# hv_in3.net
KiCad netlist of a schematic drawn in EAGLE
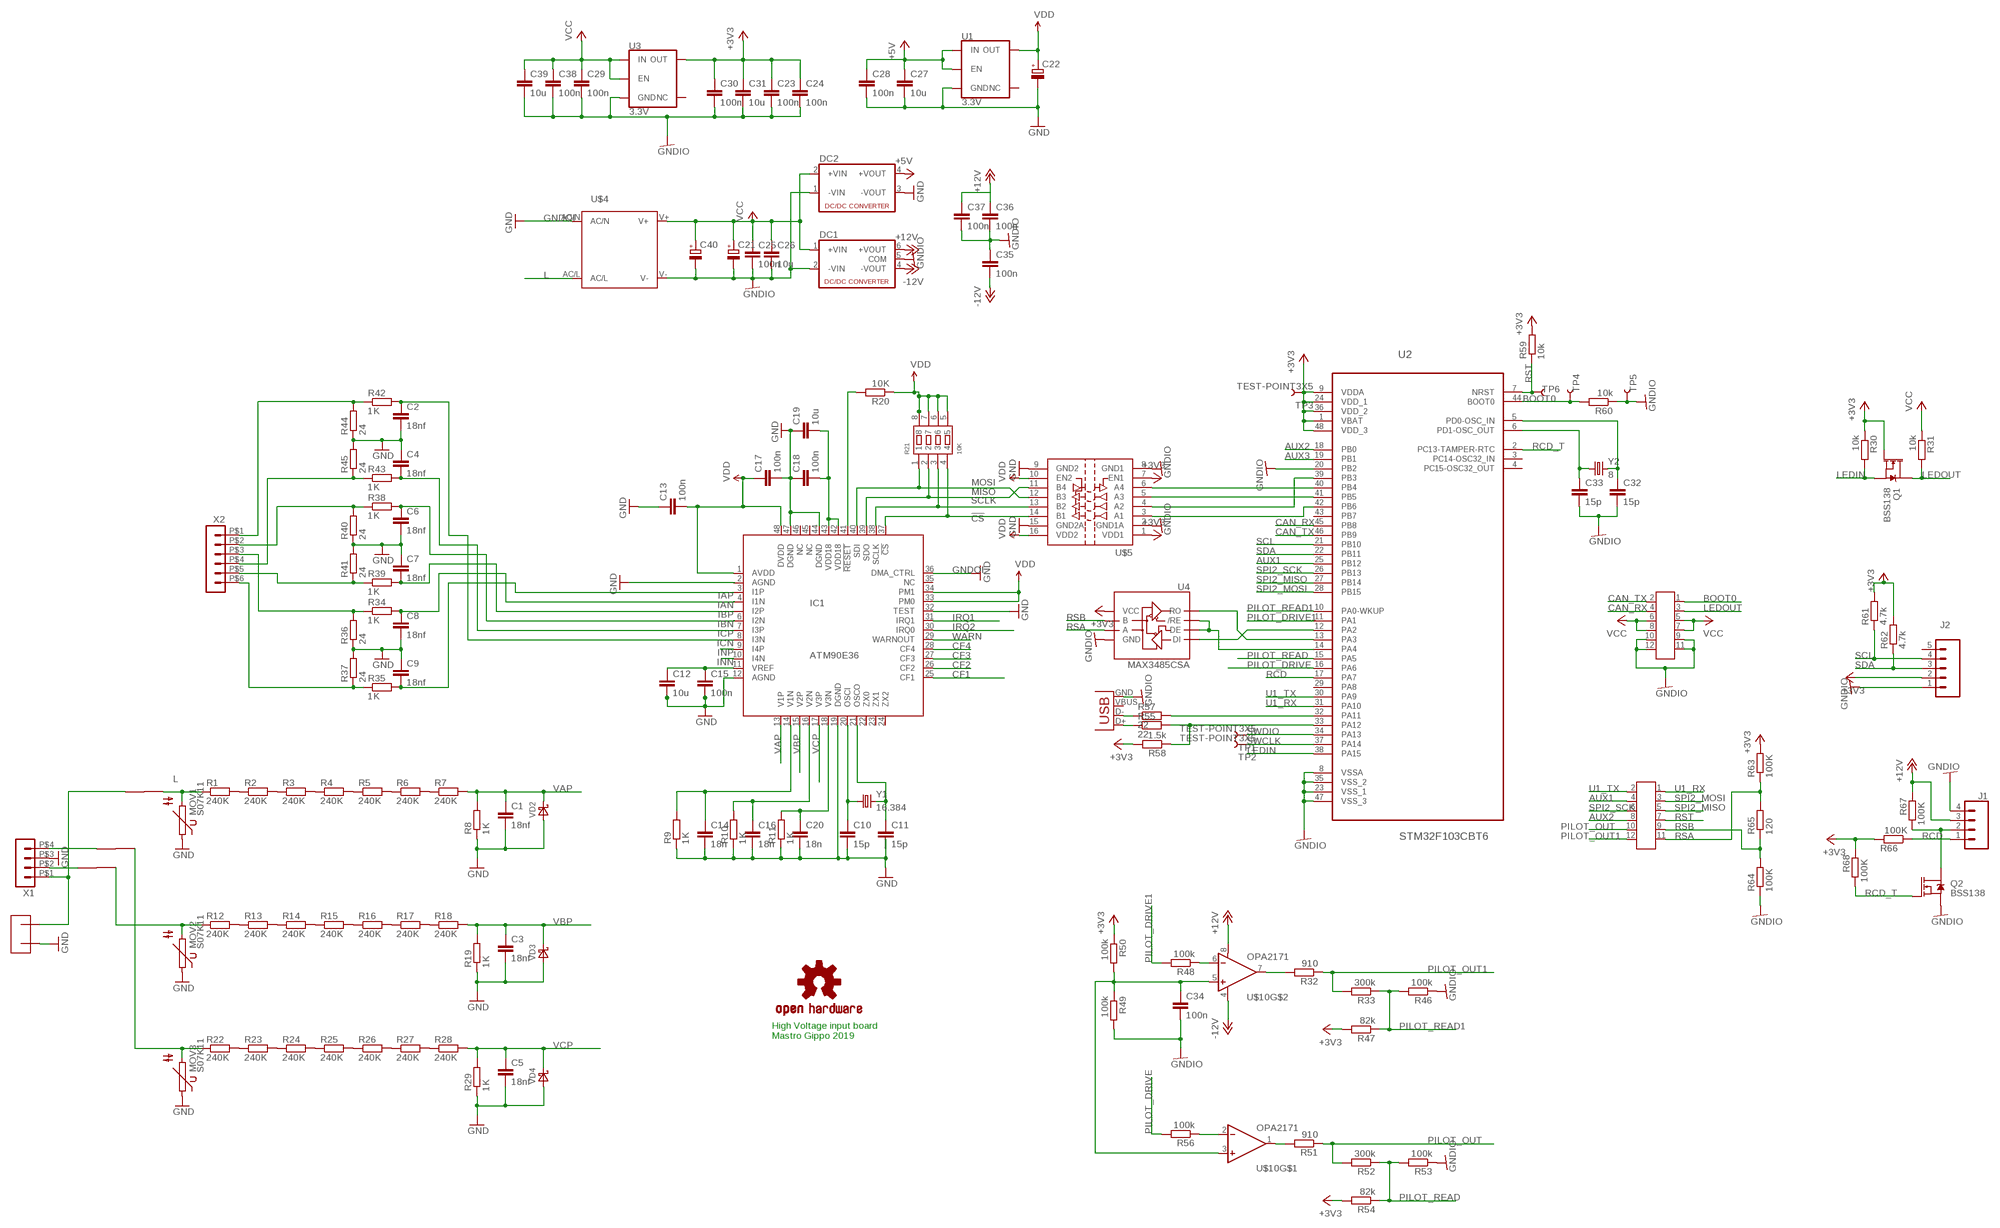
[diagram p0: schematic, sheet 1]

(export (version "E")
  (design (tool "Eeschema 10.0.6"))
  (components
    (comp (ref "C1")
      (value "18nf")
      (footprint "eagle-import:C0805K")
      (libsource (lib "eagle-import") (part "C-EUC0805K"))
    )
    (comp (ref "C2")
      (value "18nf")
      (footprint "eagle-import:C0805K")
      (libsource (lib "eagle-import") (part "C-EUC0805K"))
    )
    (comp (ref "C3")
      (value "18nf")
      (footprint "eagle-import:C0805K")
      (libsource (lib "eagle-import") (part "C-EUC0805K"))
    )
    (comp (ref "C4")
      (value "18nf")
      (footprint "eagle-import:C0805K")
      (libsource (lib "eagle-import") (part "C-EUC0805K"))
    )
    (comp (ref "C5")
      (value "18nf")
      (footprint "eagle-import:C0805K")
      (libsource (lib "eagle-import") (part "C-EUC0805K"))
    )
    (comp (ref "C6")
      (value "18nf")
      (footprint "eagle-import:C0805K")
      (libsource (lib "eagle-import") (part "C-EUC0805K"))
    )
    (comp (ref "C7")
      (value "18nf")
      (footprint "eagle-import:C0805K")
      (libsource (lib "eagle-import") (part "C-EUC0805K"))
    )
    (comp (ref "C8")
      (value "18nf")
      (footprint "eagle-import:C0805K")
      (libsource (lib "eagle-import") (part "C-EUC0805K"))
    )
    (comp (ref "C9")
      (value "18nf")
      (footprint "eagle-import:C0805K")
      (libsource (lib "eagle-import") (part "C-EUC0805K"))
    )
    (comp (ref "C10")
      (value "15p")
      (footprint "eagle-import:C0805K")
      (libsource (lib "eagle-import") (part "C-EUC0805K"))
    )
    (comp (ref "C11")
      (value "15p")
      (footprint "eagle-import:C0805K")
      (libsource (lib "eagle-import") (part "C-EUC0805K"))
    )
    (comp (ref "C12")
      (value "10u")
      (footprint "eagle-import:C0805K")
      (libsource (lib "eagle-import") (part "C-EUC0805K"))
    )
    (comp (ref "C13")
      (value "100n")
      (footprint "eagle-import:C0805K")
      (libsource (lib "eagle-import") (part "C-EUC0805K"))
    )
    (comp (ref "C14")
      (value "18n")
      (footprint "eagle-import:C0805K")
      (libsource (lib "eagle-import") (part "C-EUC0805K"))
    )
    (comp (ref "C15")
      (value "100n")
      (footprint "eagle-import:C0805K")
      (libsource (lib "eagle-import") (part "C-EUC0805K"))
    )
    (comp (ref "C16")
      (value "18n")
      (footprint "eagle-import:C0805K")
      (libsource (lib "eagle-import") (part "C-EUC0805K"))
    )
    (comp (ref "C17")
      (value "100n")
      (footprint "eagle-import:C0805K")
      (libsource (lib "eagle-import") (part "C-EUC0805K"))
    )
    (comp (ref "C18")
      (value "100n")
      (footprint "eagle-import:C0805K")
      (libsource (lib "eagle-import") (part "C-EUC0805K"))
    )
    (comp (ref "C19")
      (value "10u")
      (footprint "eagle-import:C0805K")
      (libsource (lib "eagle-import") (part "C-EUC0805K"))
    )
    (comp (ref "C20")
      (value "18n")
      (footprint "eagle-import:C0805K")
      (libsource (lib "eagle-import") (part "C-EUC0805K"))
    )
    (comp (ref "C21")
      (value "CPOL-EU153CLV-0505")
      (footprint "eagle-import:153CLV-0505")
      (libsource (lib "eagle-import") (part "CPOL-EU153CLV-0505"))
    )
    (comp (ref "C22")
      (value "CPOL-EU153CLV-0505")
      (footprint "eagle-import:153CLV-0505")
      (libsource (lib "eagle-import") (part "CPOL-EU153CLV-0505"))
    )
    (comp (ref "C23")
      (value "100n")
      (footprint "eagle-import:C0805K")
      (libsource (lib "eagle-import") (part "C-EUC0805K"))
    )
    (comp (ref "C24")
      (value "100n")
      (footprint "eagle-import:C0805K")
      (libsource (lib "eagle-import") (part "C-EUC0805K"))
    )
    (comp (ref "C25")
      (value "100n")
      (footprint "eagle-import:C0805K")
      (libsource (lib "eagle-import") (part "C-EUC0805K"))
    )
    (comp (ref "C26")
      (value "10u")
      (footprint "eagle-import:C0805K")
      (libsource (lib "eagle-import") (part "C-EUC0805K"))
    )
    (comp (ref "C27")
      (value "10u")
      (footprint "eagle-import:C0805K")
      (libsource (lib "eagle-import") (part "C-EUC0805K"))
    )
    (comp (ref "C28")
      (value "100n")
      (footprint "eagle-import:C0805K")
      (libsource (lib "eagle-import") (part "C-EUC0805K"))
    )
    (comp (ref "C29")
      (value "100n")
      (footprint "eagle-import:C0805K")
      (libsource (lib "eagle-import") (part "C-EUC0805K"))
    )
    (comp (ref "C30")
      (value "100n")
      (footprint "eagle-import:C0805K")
      (libsource (lib "eagle-import") (part "C-EUC0805K"))
    )
    (comp (ref "C31")
      (value "10u")
      (footprint "eagle-import:C0805K")
      (libsource (lib "eagle-import") (part "C-EUC0805K"))
    )
    (comp (ref "C32")
      (value "15p")
      (footprint "eagle-import:C0805K")
      (libsource (lib "eagle-import") (part "C-EUC0805K"))
    )
    (comp (ref "C33")
      (value "15p")
      (footprint "eagle-import:C0805K")
      (libsource (lib "eagle-import") (part "C-EUC0805K"))
    )
    (comp (ref "C34")
      (value "100n")
      (footprint "eagle-import:C0805K")
      (libsource (lib "eagle-import") (part "C-EUC0805K"))
    )
    (comp (ref "C35")
      (value "100n")
      (footprint "eagle-import:C0805K")
      (libsource (lib "eagle-import") (part "C-EUC0805K"))
    )
    (comp (ref "C36")
      (value "100n")
      (footprint "eagle-import:C0805K")
      (libsource (lib "eagle-import") (part "C-EUC0805K"))
    )
    (comp (ref "C37")
      (value "100n")
      (footprint "eagle-import:C0805K")
      (libsource (lib "eagle-import") (part "C-EUC0805K"))
    )
    (comp (ref "C38")
      (value "100n")
      (footprint "eagle-import:C0805K")
      (libsource (lib "eagle-import") (part "C-EUC0805K"))
    )
    (comp (ref "C39")
      (value "10u")
      (footprint "eagle-import:C0805K")
      (libsource (lib "eagle-import") (part "C-EUC0805K"))
    )
    (comp (ref "C40")
      (value "CPOL-EUB/3528-21R")
      (footprint "eagle-import:B_3528-21R")
      (libsource (lib "eagle-import") (part "CPOL-EUB/3528-21R"))
    )
    (comp (ref "DC1")
      (value "NMA")
      (footprint "eagle-import:NMA")
      (fields (field (name "MF") "C & D TECHNOLOGIES, INC") (field (name "MPN") "NMA0515SC"))
      (libsource (lib "eagle-import") (part "NMA"))
    )
    (comp (ref "DC2")
      (value "NME")
      (footprint "eagle-import:NME")
      (fields (field (name "MF") "C & D TECHNOLOGIES, INC") (field (name "MPN") "NME1205D"))
      (libsource (lib "eagle-import") (part "NME"))
    )
    (comp (ref "IC1")
      (value "ATM90E36")
      (footprint "eagle-import:TQFP48")
      (libsource (lib "eagle-import") (part "ATM90E36"))
    )
    (comp (ref "J1")
      (value "CONN_04SMD2")
      (footprint "eagle-import:1X04_1MM_RA")
      (libsource (lib "eagle-import") (part "CONN_04SMD2"))
    )
    (comp (ref "J2")
      (value "CONN_05SMD2")
      (footprint "eagle-import:1X05_1MM_RA")
      (libsource (lib "eagle-import") (part "CONN_05SMD2"))
    )
    (comp (ref "MOV1")
      (value "S07K11")
      (footprint "eagle-import:S07K11")
      (libsource (lib "eagle-import") (part "S07K11"))
    )
    (comp (ref "MOV2")
      (value "S07K11")
      (footprint "eagle-import:S07K11")
      (libsource (lib "eagle-import") (part "S07K11"))
    )
    (comp (ref "MOV3")
      (value "S07K11")
      (footprint "eagle-import:S07K11")
      (libsource (lib "eagle-import") (part "S07K11"))
    )
    (comp (ref "Q1")
      (value "BSS138")
      (footprint "eagle-import:SOT23-3")
      (libsource (lib "eagle-import") (part "MOSFET-NCH-BSS138"))
    )
    (comp (ref "Q2")
      (value "BSS138")
      (footprint "eagle-import:SOT23-3")
      (libsource (lib "eagle-import") (part "MOSFET-NCH-BSS138"))
    )
    (comp (ref "R1")
      (value "240K")
      (footprint "eagle-import:R0805")
      (libsource (lib "eagle-import") (part "R_EU"))
    )
    (comp (ref "R2")
      (value "240K")
      (footprint "eagle-import:R0805")
      (libsource (lib "eagle-import") (part "R_EU"))
    )
    (comp (ref "R3")
      (value "240K")
      (footprint "eagle-import:R0805")
      (libsource (lib "eagle-import") (part "R_EU"))
    )
    (comp (ref "R4")
      (value "240K")
      (footprint "eagle-import:R0805")
      (libsource (lib "eagle-import") (part "R_EU"))
    )
    (comp (ref "R5")
      (value "240K")
      (footprint "eagle-import:R0805")
      (libsource (lib "eagle-import") (part "R_EU"))
    )
    (comp (ref "R6")
      (value "240K")
      (footprint "eagle-import:R0805")
      (libsource (lib "eagle-import") (part "R_EU"))
    )
    (comp (ref "R7")
      (value "240K")
      (footprint "eagle-import:R0805")
      (libsource (lib "eagle-import") (part "R_EU"))
    )
    (comp (ref "R8")
      (value "1K")
      (footprint "eagle-import:R0805")
      (libsource (lib "eagle-import") (part "R_EU"))
    )
    (comp (ref "R9")
      (value "1K")
      (footprint "eagle-import:R0805")
      (libsource (lib "eagle-import") (part "R_EU"))
    )
    (comp (ref "R10")
      (value "1K")
      (footprint "eagle-import:R0805")
      (libsource (lib "eagle-import") (part "R_EU"))
    )
    (comp (ref "R11")
      (value "1K")
      (footprint "eagle-import:R0805")
      (libsource (lib "eagle-import") (part "R_EU"))
    )
    (comp (ref "R12")
      (value "240K")
      (footprint "eagle-import:R0805")
      (libsource (lib "eagle-import") (part "R_EU"))
    )
    (comp (ref "R13")
      (value "240K")
      (footprint "eagle-import:R0805")
      (libsource (lib "eagle-import") (part "R_EU"))
    )
    (comp (ref "R14")
      (value "240K")
      (footprint "eagle-import:R0805")
      (libsource (lib "eagle-import") (part "R_EU"))
    )
    (comp (ref "R15")
      (value "240K")
      (footprint "eagle-import:R0805")
      (libsource (lib "eagle-import") (part "R_EU"))
    )
    (comp (ref "R16")
      (value "240K")
      (footprint "eagle-import:R0805")
      (libsource (lib "eagle-import") (part "R_EU"))
    )
    (comp (ref "R17")
      (value "240K")
      (footprint "eagle-import:R0805")
      (libsource (lib "eagle-import") (part "R_EU"))
    )
    (comp (ref "R18")
      (value "240K")
      (footprint "eagle-import:R0805")
      (libsource (lib "eagle-import") (part "R_EU"))
    )
    (comp (ref "R19")
      (value "1K")
      (footprint "eagle-import:R0805")
      (libsource (lib "eagle-import") (part "R_EU"))
    )
    (comp (ref "R20")
      (value "10K")
      (footprint "eagle-import:R0805")
      (libsource (lib "eagle-import") (part "R_EU"))
    )
    (comp (ref "R21")
      (value "10K")
      (footprint "eagle-import:RA1206-8")
      (fields (field (name "MPN") "Chip-Array-Series-1%"))
      (libsource (lib "eagle-import") (part "SMD-RES-ARRAY-1K-4R(RA1206-8)"))
    )
    (comp (ref "R22")
      (value "240K")
      (footprint "eagle-import:R0805")
      (libsource (lib "eagle-import") (part "R_EU"))
    )
    (comp (ref "R23")
      (value "240K")
      (footprint "eagle-import:R0805")
      (libsource (lib "eagle-import") (part "R_EU"))
    )
    (comp (ref "R24")
      (value "240K")
      (footprint "eagle-import:R0805")
      (libsource (lib "eagle-import") (part "R_EU"))
    )
    (comp (ref "R25")
      (value "240K")
      (footprint "eagle-import:R0805")
      (libsource (lib "eagle-import") (part "R_EU"))
    )
    (comp (ref "R26")
      (value "240K")
      (footprint "eagle-import:R0805")
      (libsource (lib "eagle-import") (part "R_EU"))
    )
    (comp (ref "R27")
      (value "240K")
      (footprint "eagle-import:R0805")
      (libsource (lib "eagle-import") (part "R_EU"))
    )
    (comp (ref "R28")
      (value "240K")
      (footprint "eagle-import:R0805")
      (libsource (lib "eagle-import") (part "R_EU"))
    )
    (comp (ref "R29")
      (value "1K")
      (footprint "eagle-import:R0805")
      (libsource (lib "eagle-import") (part "R_EU"))
    )
    (comp (ref "R30")
      (value "10k")
      (footprint "eagle-import:R0805")
      (libsource (lib "eagle-import") (part "R-EU_R0805"))
    )
    (comp (ref "R31")
      (value "10k")
      (footprint "eagle-import:R0805")
      (libsource (lib "eagle-import") (part "R-EU_R0805"))
    )
    (comp (ref "R32")
      (value "910")
      (footprint "eagle-import:R1206")
      (libsource (lib "eagle-import") (part "R-EU_R1206"))
    )
    (comp (ref "R33")
      (value "300k")
      (footprint "eagle-import:R0805")
      (libsource (lib "eagle-import") (part "R-EU_R0805"))
    )
    (comp (ref "R34")
      (value "1K")
      (footprint "eagle-import:R0805")
      (libsource (lib "eagle-import") (part "R_EU"))
    )
    (comp (ref "R35")
      (value "1K")
      (footprint "eagle-import:R0805")
      (libsource (lib "eagle-import") (part "R_EU"))
    )
    (comp (ref "R36")
      (value "24")
      (footprint "eagle-import:R0805")
      (libsource (lib "eagle-import") (part "R_EU"))
    )
    (comp (ref "R37")
      (value "24")
      (footprint "eagle-import:R0805")
      (libsource (lib "eagle-import") (part "R_EU"))
    )
    (comp (ref "R38")
      (value "1K")
      (footprint "eagle-import:R0805")
      (libsource (lib "eagle-import") (part "R_EU"))
    )
    (comp (ref "R39")
      (value "1K")
      (footprint "eagle-import:R0805")
      (libsource (lib "eagle-import") (part "R_EU"))
    )
    (comp (ref "R40")
      (value "24")
      (footprint "eagle-import:R0805")
      (libsource (lib "eagle-import") (part "R_EU"))
    )
    (comp (ref "R41")
      (value "24")
      (footprint "eagle-import:R0805")
      (libsource (lib "eagle-import") (part "R_EU"))
    )
    (comp (ref "R42")
      (value "1K")
      (footprint "eagle-import:R0805")
      (libsource (lib "eagle-import") (part "R_EU"))
    )
    (comp (ref "R43")
      (value "1K")
      (footprint "eagle-import:R0805")
      (libsource (lib "eagle-import") (part "R_EU"))
    )
    (comp (ref "R44")
      (value "24")
      (footprint "eagle-import:R0805")
      (libsource (lib "eagle-import") (part "R_EU"))
    )
    (comp (ref "R45")
      (value "24")
      (footprint "eagle-import:R0805")
      (libsource (lib "eagle-import") (part "R_EU"))
    )
    (comp (ref "R46")
      (value "100k")
      (footprint "eagle-import:R0805")
      (libsource (lib "eagle-import") (part "R-EU_R0805"))
    )
    (comp (ref "R47")
      (value "82k")
      (footprint "eagle-import:R0805")
      (libsource (lib "eagle-import") (part "R-EU_R0805"))
    )
    (comp (ref "R48")
      (value "100k")
      (footprint "eagle-import:R0805")
      (libsource (lib "eagle-import") (part "R-EU_R0805"))
    )
    (comp (ref "R49")
      (value "100k")
      (footprint "eagle-import:R0805")
      (libsource (lib "eagle-import") (part "R-EU_R0805"))
    )
    (comp (ref "R50")
      (value "100k")
      (footprint "eagle-import:R0805")
      (libsource (lib "eagle-import") (part "R-EU_R0805"))
    )
    (comp (ref "R51")
      (value "910")
      (footprint "eagle-import:R1206")
      (libsource (lib "eagle-import") (part "R-EU_R1206"))
    )
    (comp (ref "R52")
      (value "300k")
      (footprint "eagle-import:R0805")
      (libsource (lib "eagle-import") (part "R-EU_R0805"))
    )
    (comp (ref "R53")
      (value "100k")
      (footprint "eagle-import:R0805")
      (libsource (lib "eagle-import") (part "R-EU_R0805"))
    )
    (comp (ref "R54")
      (value "82k")
      (footprint "eagle-import:R0805")
      (libsource (lib "eagle-import") (part "R-EU_R0805"))
    )
    (comp (ref "R55")
      (value "22")
      (footprint "eagle-import:R0805")
      (libsource (lib "eagle-import") (part "R-EU_R0805"))
    )
    (comp (ref "R56")
      (value "100k")
      (footprint "eagle-import:R0805")
      (libsource (lib "eagle-import") (part "R-EU_R0805"))
    )
    (comp (ref "R57")
      (value "22")
      (footprint "eagle-import:R0805")
      (libsource (lib "eagle-import") (part "R-EU_R0805"))
    )
    (comp (ref "R58")
      (value "1.5k")
      (footprint "eagle-import:R0805")
      (libsource (lib "eagle-import") (part "R-EU_R0805"))
    )
    (comp (ref "R59")
      (value "10k")
      (footprint "eagle-import:R0805")
      (libsource (lib "eagle-import") (part "R-EU_R0805"))
    )
    (comp (ref "R60")
      (value "10k")
      (footprint "eagle-import:R0805")
      (libsource (lib "eagle-import") (part "R-EU_R0805"))
    )
    (comp (ref "R61")
      (value "4.7k")
      (footprint "eagle-import:R0805")
      (libsource (lib "eagle-import") (part "R-EU_R0805"))
    )
    (comp (ref "R62")
      (value "4.7k")
      (footprint "eagle-import:R0805")
      (libsource (lib "eagle-import") (part "R-EU_R0805"))
    )
    (comp (ref "R63")
      (value "100K")
      (footprint "eagle-import:R0805")
      (libsource (lib "eagle-import") (part "R-EU_R0805"))
    )
    (comp (ref "R64")
      (value "100K")
      (footprint "eagle-import:R0805")
      (libsource (lib "eagle-import") (part "R-EU_R0805"))
    )
    (comp (ref "R65")
      (value "120")
      (footprint "eagle-import:R0805")
      (libsource (lib "eagle-import") (part "R-EU_R0805"))
    )
    (comp (ref "R66")
      (value "100K")
      (footprint "eagle-import:R0805")
      (libsource (lib "eagle-import") (part "R-EU_R0805"))
    )
    (comp (ref "R67")
      (value "100K")
      (footprint "eagle-import:R0805")
      (libsource (lib "eagle-import") (part "R-EU_R0805"))
    )
    (comp (ref "R68")
      (value "100K")
      (footprint "eagle-import:R0805")
      (libsource (lib "eagle-import") (part "R-EU_R0805"))
    )
    (comp (ref "TP1")
      (value "TEST-POINT3X5")
      (footprint "eagle-import:PAD.03X.05")
      (libsource (lib "eagle-import") (part "TEST-POINT3X5"))
    )
    (comp (ref "TP2")
      (value "TEST-POINT3X5")
      (footprint "eagle-import:PAD.03X.05")
      (libsource (lib "eagle-import") (part "TEST-POINT3X5"))
    )
    (comp (ref "TP3")
      (value "TEST-POINT3X5")
      (footprint "eagle-import:PAD.03X.05")
      (libsource (lib "eagle-import") (part "TEST-POINT3X5"))
    )
    (comp (ref "TP4")
      (value "TEST-POINT3X5")
      (footprint "eagle-import:PAD.03X.05")
      (libsource (lib "eagle-import") (part "TEST-POINT3X5"))
    )
    (comp (ref "TP5")
      (value "TEST-POINT3X5")
      (footprint "eagle-import:PAD.03X.05")
      (libsource (lib "eagle-import") (part "TEST-POINT3X5"))
    )
    (comp (ref "TP6")
      (value "TEST-POINT3X5")
      (footprint "eagle-import:PAD.03X.05")
      (libsource (lib "eagle-import") (part "TEST-POINT3X5"))
    )
    (comp (ref "U$1")
      (value "FUSE_2410")
      (footprint "eagle-import:2410_F")
      (libsource (lib "eagle-import") (part "FUSE_2410"))
    )
    (comp (ref "U$2")
      (value "FUSE_2410")
      (footprint "eagle-import:2410_F")
      (libsource (lib "eagle-import") (part "FUSE_2410"))
    )
    (comp (ref "U$3")
      (value "FUSE_2410")
      (footprint "eagle-import:2410_F")
      (libsource (lib "eagle-import") (part "FUSE_2410"))
    )
    (comp (ref "U$4")
      (value "IRM_15/20IRM_15/20")
      (footprint "eagle-import:IRM_15_20")
      (libsource (lib "eagle-import") (part "IRM_15/20IRM_15/20"))
    )
    (comp (ref "U$5")
      (value "SI8441IS1")
      (footprint "eagle-import:SO16")
      (libsource (lib "eagle-import") (part "SI8441IS1"))
    )
    (comp (ref "U$6")
      (value "ISOLATED_2P")
      (footprint "eagle-import:STRIP_NOMIDDLE")
      (libsource (lib "eagle-import") (part "ISOLATED_2P"))
    )
    (comp (ref "U$7")
      (value "CLP-106-02-F-D-P")
      (footprint "eagle-import:CLP-106-02-X-D")
      (libsource (lib "eagle-import") (part "CLP-106-02-F-D-P"))
    )
    (comp (ref "U$8")
      (value "CLP-106-02-F-D-P")
      (footprint "eagle-import:CLP-106-02-X-D")
      (libsource (lib "eagle-import") (part "CLP-106-02-F-D-P"))
    )
    (comp (ref "U$9")
      (value "OSHW-LOGOS")
      (footprint "eagle-import:OSHW-LOGO-S")
      (libsource (lib "eagle-import") (part "OSHW-LOGOS"))
    )
    (comp (ref "U$10")
      (value "OPA2171")
      (footprint "eagle-import:SO08")
      (libsource (lib "eagle-import") (part "OPA2171"))
    )
    (comp (ref "U1")
      (value "3.3V")
      (footprint "eagle-import:SOT23-5")
      (libsource (lib "eagle-import") (part "V_REG_AP2112K-3.3V"))
    )
    (comp (ref "U2")
      (value "STM32F103CBT6")
      (footprint "eagle-import:QFP50P900X900X160-48N")
      (libsource (lib "eagle-import") (part "STM32F103CBT6"))
    )
    (comp (ref "U3")
      (value "3.3V")
      (footprint "eagle-import:SOT23-5")
      (libsource (lib "eagle-import") (part "V_REG_AP2112K-3.3V"))
    )
    (comp (ref "U4")
      (value "MAX3485CSA")
      (footprint "eagle-import:SO08")
      (libsource (lib "eagle-import") (part "RS485SOIC"))
    )
    (comp (ref "VD2")
      (value "DIODE-SCHOTTKY-SOD523")
      (footprint "eagle-import:SOD523")
      (libsource (lib "eagle-import") (part "DIODE-SCHOTTKY-SOD523"))
    )
    (comp (ref "VD3")
      (value "DIODE-SCHOTTKY-SOD523")
      (footprint "eagle-import:SOD523")
      (libsource (lib "eagle-import") (part "DIODE-SCHOTTKY-SOD523"))
    )
    (comp (ref "VD4")
      (value "DIODE-SCHOTTKY-SOD523")
      (footprint "eagle-import:SOD523")
      (libsource (lib "eagle-import") (part "DIODE-SCHOTTKY-SOD523"))
    )
    (comp (ref "X1")
      (value "HEADER_POS4_43045-0401")
      (footprint "eagle-import:43045-0400")
      (libsource (lib "eagle-import") (part "HEADER_POS4_?43045-0401"))
    )
    (comp (ref "X2")
      (value "HEADER_POS6_43045-0600")
      (footprint "eagle-import:43045-0600")
      (libsource (lib "eagle-import") (part "HEADER_POS6_?43045-0600"))
    )
    (comp (ref "X3")
      (value "USB-MICROB")
      (footprint "eagle-import:USB-MICROB")
      (libsource (lib "eagle-import") (part "USB-MICROB"))
    )
    (comp (ref "Y1")
      (value "16.384")
      (footprint "eagle-import:CRYSTAL-SMD-3.2X2.5MM")
      (libsource (lib "eagle-import") (part "CRYSTALSMD-3.2X2.5"))
    )
    (comp (ref "Y2")
      (value "8")
      (footprint "eagle-import:CRYSTAL-SMD-3.2X2.5MM")
      (libsource (lib "eagle-import") (part "CRYSTALSMD-3.2X2.5"))
    )
  )
  (nets
    (net (code "1") (name "+3V3") (class "Default")
      (node (ref "C23") (pin "1") (pinfunction "1_1") (pintype "passive"))
      (node (ref "C24") (pin "1") (pinfunction "1_1") (pintype "passive"))
      (node (ref "C30") (pin "1") (pinfunction "1_1") (pintype "passive"))
      (node (ref "C31") (pin "1") (pinfunction "1_1") (pintype "passive"))
      (node (ref "J2") (pin "2") (pinfunction "2_2") (pintype "passive"))
      (node (ref "Q1") (pin "1") (pinfunction "G_1") (pintype "bidirectional"))
      (node (ref "R30") (pin "1") (pinfunction "1_1") (pintype "passive"))
      (node (ref "R47") (pin "2") (pinfunction "2_2") (pintype "passive"))
      (node (ref "R50") (pin "1") (pinfunction "1_1") (pintype "passive"))
      (node (ref "R54") (pin "2") (pinfunction "2_2") (pintype "passive"))
      (node (ref "R58") (pin "2") (pinfunction "2_2") (pintype "passive"))
      (node (ref "R59") (pin "2") (pinfunction "2_2") (pintype "passive"))
      (node (ref "R61") (pin "2") (pinfunction "2_2") (pintype "passive"))
      (node (ref "R62") (pin "2") (pinfunction "2_2") (pintype "passive"))
      (node (ref "R63") (pin "2") (pinfunction "2_2") (pintype "passive"))
      (node (ref "R66") (pin "2") (pinfunction "2_2") (pintype "passive"))
      (node (ref "R68") (pin "2") (pinfunction "2_2") (pintype "passive"))
      (node (ref "TP3") (pin "P$1") (pinfunction "1_P$1") (pintype "bidirectional"))
      (node (ref "U$5") (pin "1") (pinfunction "VDD1_1") (pintype "power_in"))
      (node (ref "U$5") (pin "7") (pinfunction "EN1_7") (pintype "input"))
      (node (ref "U2") (pin "1") (pinfunction "VBAT_1") (pintype "input"))
      (node (ref "U2") (pin "24") (pinfunction "VDD_1_24") (pintype "bidirectional"))
      (node (ref "U2") (pin "36") (pinfunction "VDD_2_36") (pintype "power_in"))
      (node (ref "U2") (pin "48") (pinfunction "VDD_3_48") (pintype "power_in"))
      (node (ref "U2") (pin "9") (pinfunction "VDDA_9") (pintype "power_in"))
      (node (ref "U3") (pin "5") (pinfunction "OUT_5") (pintype "passive"))
      (node (ref "U4") (pin "8") (pinfunction "VCC_8") (pintype "bidirectional"))
    )
    (net (code "2") (name "+5V") (class "Default")
      (node (ref "C27") (pin "1") (pinfunction "1_1") (pintype "passive"))
      (node (ref "C28") (pin "1") (pinfunction "1_1") (pintype "passive"))
      (node (ref "DC2") (pin "4") (pinfunction "+VOUT_4") (pintype "passive"))
      (node (ref "U1") (pin "1") (pinfunction "IN_1") (pintype "input"))
      (node (ref "U1") (pin "3") (pinfunction "EN_3") (pintype "input"))
    )
    (net (code "3") (name "+12V") (class "Default")
      (node (ref "C36") (pin "1") (pinfunction "1_1") (pintype "passive"))
      (node (ref "C37") (pin "1") (pinfunction "1_1") (pintype "passive"))
      (node (ref "DC1") (pin "6") (pinfunction "+VOUT_6") (pintype "passive"))
      (node (ref "J1") (pin "3") (pinfunction "3_3") (pintype "passive"))
      (node (ref "R67") (pin "2") (pinfunction "2_2") (pintype "passive"))
      (node (ref "U$10") (pin "8") (pinfunction "V+_8") (pintype "power_in"))
    )
    (net (code "4") (name "-12V") (class "Default")
      (node (ref "C35") (pin "2") (pinfunction "2_2") (pintype "passive"))
      (node (ref "DC1") (pin "4") (pinfunction "-VOUT_4") (pintype "passive"))
      (node (ref "U$10") (pin "4") (pinfunction "V-_4") (pintype "power_in"))
    )
    (net (code "5") (name "/AUX1") (class "Default")
      (node (ref "U$7") (pin "4") (pinfunction "P$4_4") (pintype "bidirectional"))
      (node (ref "U2") (pin "25") (pinfunction "PB12_25") (pintype "bidirectional"))
    )
    (net (code "6") (name "/AUX2") (class "Default")
      (node (ref "U$7") (pin "8") (pinfunction "P$8_8") (pintype "bidirectional"))
      (node (ref "U2") (pin "18") (pinfunction "PB0_18") (pintype "bidirectional"))
    )
    (net (code "7") (name "/AUX3") (class "Default")
      (node (ref "U2") (pin "19") (pinfunction "PB1_19") (pintype "bidirectional"))
    )
    (net (code "8") (name "/BOOT0") (class "Default")
      (node (ref "R60") (pin "2") (pinfunction "2_2") (pintype "passive"))
      (node (ref "TP4") (pin "P$1") (pinfunction "1_P$1") (pintype "bidirectional"))
      (node (ref "U$8") (pin "1") (pinfunction "P$1_1") (pintype "bidirectional"))
      (node (ref "U2") (pin "44") (pinfunction "BOOT0_44") (pintype "bidirectional"))
    )
    (net (code "9") (name "/CAN_RX") (class "Default")
      (node (ref "U$8") (pin "4") (pinfunction "P$4_4") (pintype "bidirectional"))
      (node (ref "U2") (pin "45") (pinfunction "PB8_45") (pintype "bidirectional"))
    )
    (net (code "10") (name "/CAN_TX") (class "Default")
      (node (ref "U$8") (pin "2") (pinfunction "P$2_2") (pintype "bidirectional"))
      (node (ref "U2") (pin "46") (pinfunction "PB9_46") (pintype "bidirectional"))
    )
    (net (code "11") (name "/CF1") (class "Default")
      (node (ref "IC1") (pin "25") (pinfunction "CF1_25") (pintype "output"))
    )
    (net (code "12") (name "/CF2") (class "Default")
      (node (ref "IC1") (pin "26") (pinfunction "CF2_26") (pintype "output"))
    )
    (net (code "13") (name "/CF3") (class "Default")
      (node (ref "IC1") (pin "27") (pinfunction "CF3_27") (pintype "output"))
    )
    (net (code "14") (name "/CF4") (class "Default")
      (node (ref "IC1") (pin "28") (pinfunction "CF4_28") (pintype "output"))
    )
    (net (code "15") (name "/IAN") (class "Default")
      (node (ref "C8") (pin "1") (pinfunction "1_1") (pintype "passive"))
      (node (ref "IC1") (pin "4") (pinfunction "I1N_4") (pintype "input"))
      (node (ref "R34") (pin "2") (pinfunction "2_2") (pintype "passive"))
    )
    (net (code "16") (name "/IAP") (class "Default")
      (node (ref "C9") (pin "2") (pinfunction "2_2") (pintype "passive"))
      (node (ref "IC1") (pin "3") (pinfunction "I1P_3") (pintype "input"))
      (node (ref "R35") (pin "2") (pinfunction "2_2") (pintype "passive"))
    )
    (net (code "17") (name "/IBN") (class "Default")
      (node (ref "C6") (pin "1") (pinfunction "1_1") (pintype "passive"))
      (node (ref "IC1") (pin "6") (pinfunction "I2N_6") (pintype "input"))
      (node (ref "R38") (pin "2") (pinfunction "2_2") (pintype "passive"))
    )
    (net (code "18") (name "/IBP") (class "Default")
      (node (ref "C7") (pin "2") (pinfunction "2_2") (pintype "passive"))
      (node (ref "IC1") (pin "5") (pinfunction "I2P_5") (pintype "input"))
      (node (ref "R39") (pin "2") (pinfunction "2_2") (pintype "passive"))
    )
    (net (code "19") (name "/ICN") (class "Default")
      (node (ref "C2") (pin "1") (pinfunction "1_1") (pintype "passive"))
      (node (ref "IC1") (pin "8") (pinfunction "I3N_8") (pintype "input"))
      (node (ref "R42") (pin "2") (pinfunction "2_2") (pintype "passive"))
    )
    (net (code "20") (name "/ICP") (class "Default")
      (node (ref "C4") (pin "2") (pinfunction "2_2") (pintype "passive"))
      (node (ref "IC1") (pin "7") (pinfunction "I3P_7") (pintype "input"))
      (node (ref "R43") (pin "2") (pinfunction "2_2") (pintype "passive"))
    )
    (net (code "21") (name "/INN") (class "Default")
      (node (ref "IC1") (pin "10") (pinfunction "I4N_10") (pintype "input"))
    )
    (net (code "22") (name "/INP") (class "Default")
      (node (ref "IC1") (pin "9") (pinfunction "I4P_9") (pintype "input"))
    )
    (net (code "23") (name "/IRQ1") (class "Default")
      (node (ref "IC1") (pin "31") (pinfunction "IRQ1_31") (pintype "output"))
    )
    (net (code "24") (name "/IRQ2") (class "Default")
      (node (ref "IC1") (pin "30") (pinfunction "IRQ0_30") (pintype "output"))
    )
    (net (code "25") (name "/L") (class "Default")
      (node (ref "MOV1") (pin "2") (pinfunction "2_2") (pintype "passive"))
      (node (ref "R1") (pin "1") (pinfunction "1_1") (pintype "passive"))
      (node (ref "U$1") (pin "P$2") (pinfunction "P$2_P$2") (pintype "bidirectional"))
      (node (ref "U$4") (pin "AC/L") (pinfunction "AC/L_AC/L") (pintype "input"))
    )
    (net (code "26") (name "/LEDIN") (class "Default")
      (node (ref "Q1") (pin "2") (pinfunction "S_2") (pintype "bidirectional"))
      (node (ref "R30") (pin "2") (pinfunction "2_2") (pintype "passive"))
      (node (ref "U2") (pin "38") (pinfunction "PA15_38") (pintype "bidirectional"))
    )
    (net (code "27") (name "/LEDOUT") (class "Default")
      (node (ref "Q1") (pin "3") (pinfunction "D_3") (pintype "bidirectional"))
      (node (ref "R31") (pin "2") (pinfunction "2_2") (pintype "passive"))
      (node (ref "U$8") (pin "3") (pinfunction "P$3_3") (pintype "bidirectional"))
    )
    (net (code "28") (name "/MISO") (class "Default")
      (node (ref "IC1") (pin "39") (pinfunction "SDO_39") (pintype "output"))
      (node (ref "R21") (pin "2") (pinfunction "2_2") (pintype "bidirectional"))
      (node (ref "U$5") (pin "11") (pinfunction "B4_11") (pintype "output"))
    )
    (net (code "29") (name "/MOSI") (class "Default")
      (node (ref "IC1") (pin "40") (pinfunction "SDI_40") (pintype "input"))
      (node (ref "R21") (pin "1") (pinfunction "1_1") (pintype "bidirectional"))
      (node (ref "U$5") (pin "12") (pinfunction "B3_12") (pintype "output"))
    )
    (net (code "30") (name "/PILOT_DRIVE") (class "Default")
      (node (ref "R56") (pin "2") (pinfunction "2_2") (pintype "passive"))
      (node (ref "U2") (pin "16") (pinfunction "PA6_16") (pintype "bidirectional"))
    )
    (net (code "31") (name "/PILOT_DRIVE1") (class "Default")
      (node (ref "R48") (pin "2") (pinfunction "2_2") (pintype "passive"))
      (node (ref "U2") (pin "11") (pinfunction "PA1_11") (pintype "bidirectional"))
    )
    (net (code "32") (name "/PILOT_OUT") (class "Default")
      (node (ref "R51") (pin "1") (pinfunction "1_1") (pintype "passive"))
      (node (ref "R52") (pin "2") (pinfunction "2_2") (pintype "passive"))
      (node (ref "U$7") (pin "10") (pinfunction "P$10_10") (pintype "bidirectional"))
    )
    (net (code "33") (name "/PILOT_OUT1") (class "Default")
      (node (ref "R32") (pin "1") (pinfunction "1_1") (pintype "passive"))
      (node (ref "R33") (pin "2") (pinfunction "2_2") (pintype "passive"))
      (node (ref "U$7") (pin "12") (pinfunction "P$12_12") (pintype "bidirectional"))
    )
    (net (code "34") (name "/PILOT_READ") (class "Default")
      (node (ref "R52") (pin "1") (pinfunction "1_1") (pintype "passive"))
      (node (ref "R53") (pin "2") (pinfunction "2_2") (pintype "passive"))
      (node (ref "R54") (pin "1") (pinfunction "1_1") (pintype "passive"))
      (node (ref "U2") (pin "15") (pinfunction "PA5_15") (pintype "bidirectional"))
    )
    (net (code "35") (name "/PILOT_READ1") (class "Default")
      (node (ref "R33") (pin "1") (pinfunction "1_1") (pintype "passive"))
      (node (ref "R46") (pin "2") (pinfunction "2_2") (pintype "passive"))
      (node (ref "R47") (pin "1") (pinfunction "1_1") (pintype "passive"))
      (node (ref "U2") (pin "10") (pinfunction "PA0-WKUP_10") (pintype "bidirectional"))
    )
    (net (code "36") (name "/RCD") (class "Default")
      (node (ref "J1") (pin "1") (pinfunction "1_1") (pintype "passive"))
      (node (ref "R66") (pin "1") (pinfunction "1_1") (pintype "passive"))
      (node (ref "U2") (pin "17") (pinfunction "PA7_17") (pintype "bidirectional"))
    )
    (net (code "37") (name "/RCD_T") (class "Default")
      (node (ref "Q2") (pin "1") (pinfunction "G_1") (pintype "bidirectional"))
      (node (ref "R68") (pin "1") (pinfunction "1_1") (pintype "passive"))
      (node (ref "U2") (pin "2") (pinfunction "PC13-TAMPER-RTC_2") (pintype "bidirectional"))
    )
    (net (code "38") (name "/RSA") (class "Default")
      (node (ref "R63") (pin "1") (pinfunction "1_1") (pintype "passive"))
      (node (ref "R65") (pin "2") (pinfunction "2_2") (pintype "passive"))
      (node (ref "U$7") (pin "11") (pinfunction "P$11_11") (pintype "bidirectional"))
      (node (ref "U4") (pin "6") (pinfunction "A_6") (pintype "bidirectional"))
    )
    (net (code "39") (name "/RSB") (class "Default")
      (node (ref "R64") (pin "2") (pinfunction "2_2") (pintype "passive"))
      (node (ref "R65") (pin "1") (pinfunction "1_1") (pintype "passive"))
      (node (ref "U$7") (pin "9") (pinfunction "P$9_9") (pintype "bidirectional"))
      (node (ref "U4") (pin "7") (pinfunction "B_7") (pintype "bidirectional"))
    )
    (net (code "40") (name "/RST") (class "Default")
      (node (ref "R59") (pin "1") (pinfunction "1_1") (pintype "passive"))
      (node (ref "TP6") (pin "P$1") (pinfunction "1_P$1") (pintype "bidirectional"))
      (node (ref "U$7") (pin "7") (pinfunction "P$7_7") (pintype "bidirectional"))
      (node (ref "U2") (pin "7") (pinfunction "NRST_7") (pintype "bidirectional"))
    )
    (net (code "41") (name "/SCL") (class "Default")
      (node (ref "J2") (pin "4") (pinfunction "4_4") (pintype "passive"))
      (node (ref "R61") (pin "1") (pinfunction "1_1") (pintype "passive"))
      (node (ref "U2") (pin "21") (pinfunction "PB10_21") (pintype "bidirectional"))
    )
    (net (code "42") (name "/SCLK") (class "Default")
      (node (ref "IC1") (pin "38") (pinfunction "SCLK_38") (pintype "input"))
      (node (ref "R21") (pin "3") (pinfunction "3_3") (pintype "bidirectional"))
      (node (ref "U$5") (pin "13") (pinfunction "B2_13") (pintype "output"))
    )
    (net (code "43") (name "/SDA") (class "Default")
      (node (ref "J2") (pin "3") (pinfunction "3_3") (pintype "passive"))
      (node (ref "R62") (pin "1") (pinfunction "1_1") (pintype "passive"))
      (node (ref "U2") (pin "22") (pinfunction "PB11_22") (pintype "bidirectional"))
    )
    (net (code "44") (name "/SPI2_MISO") (class "Default")
      (node (ref "U$7") (pin "5") (pinfunction "P$5_5") (pintype "bidirectional"))
      (node (ref "U2") (pin "27") (pinfunction "PB14_27") (pintype "bidirectional"))
    )
    (net (code "45") (name "/SPI2_MOSI") (class "Default")
      (node (ref "U$7") (pin "3") (pinfunction "P$3_3") (pintype "bidirectional"))
      (node (ref "U2") (pin "28") (pinfunction "PB15_28") (pintype "bidirectional"))
    )
    (net (code "46") (name "/SPI2_SCK") (class "Default")
      (node (ref "U$7") (pin "6") (pinfunction "P$6_6") (pintype "bidirectional"))
      (node (ref "U2") (pin "26") (pinfunction "PB13_26") (pintype "bidirectional"))
    )
    (net (code "47") (name "/SWCLK") (class "Default")
      (node (ref "TP2") (pin "P$1") (pinfunction "1_P$1") (pintype "bidirectional"))
      (node (ref "U2") (pin "37") (pinfunction "PA14_37") (pintype "bidirectional"))
    )
    (net (code "48") (name "/SWDIO") (class "Default")
      (node (ref "TP1") (pin "P$1") (pinfunction "1_P$1") (pintype "bidirectional"))
      (node (ref "U2") (pin "34") (pinfunction "PA13_34") (pintype "bidirectional"))
    )
    (net (code "49") (name "/U1_RX") (class "Default")
      (node (ref "U$7") (pin "1") (pinfunction "P$1_1") (pintype "bidirectional"))
      (node (ref "U2") (pin "31") (pinfunction "PA10_31") (pintype "bidirectional"))
    )
    (net (code "50") (name "/U1_TX") (class "Default")
      (node (ref "U$7") (pin "2") (pinfunction "P$2_2") (pintype "bidirectional"))
      (node (ref "U2") (pin "30") (pinfunction "PA9_30") (pintype "bidirectional"))
    )
    (net (code "51") (name "/VAP") (class "Default")
      (node (ref "C1") (pin "1") (pinfunction "1_1") (pintype "passive"))
      (node (ref "IC1") (pin "13") (pinfunction "V1P_13") (pintype "input"))
      (node (ref "R7") (pin "2") (pinfunction "2_2") (pintype "passive"))
      (node (ref "R8") (pin "2") (pinfunction "2_2") (pintype "passive"))
      (node (ref "VD2") (pin "C") (pinfunction "C_C") (pintype "passive"))
    )
    (net (code "52") (name "/VBP") (class "Default")
      (node (ref "C3") (pin "1") (pinfunction "1_1") (pintype "passive"))
      (node (ref "IC1") (pin "15") (pinfunction "V2P_15") (pintype "input"))
      (node (ref "R18") (pin "2") (pinfunction "2_2") (pintype "passive"))
      (node (ref "R19") (pin "2") (pinfunction "2_2") (pintype "passive"))
      (node (ref "VD3") (pin "C") (pinfunction "C_C") (pintype "passive"))
    )
    (net (code "53") (name "/VCP") (class "Default")
      (node (ref "C5") (pin "1") (pinfunction "1_1") (pintype "passive"))
      (node (ref "IC1") (pin "17") (pinfunction "V3P_17") (pintype "input"))
      (node (ref "R28") (pin "2") (pinfunction "2_2") (pintype "passive"))
      (node (ref "R29") (pin "2") (pinfunction "2_2") (pintype "passive"))
      (node (ref "VD4") (pin "C") (pinfunction "C_C") (pintype "passive"))
    )
    (net (code "54") (name "/WARN") (class "Default")
      (node (ref "IC1") (pin "29") (pinfunction "WARNOUT_29") (pintype "output"))
    )
    (net (code "55") (name "/~{CS}") (class "Default")
      (node (ref "IC1") (pin "37") (pinfunction "~{CS}_37") (pintype "input"))
      (node (ref "R21") (pin "4") (pinfunction "4_4") (pintype "bidirectional"))
      (node (ref "U$5") (pin "14") (pinfunction "B1_14") (pintype "output"))
    )
    (net (code "56") (name "GND") (class "Default")
      (node (ref "C1") (pin "2") (pinfunction "2_2") (pintype "passive"))
      (node (ref "C10") (pin "2") (pinfunction "2_2") (pintype "passive"))
      (node (ref "C11") (pin "2") (pinfunction "2_2") (pintype "passive"))
      (node (ref "C12") (pin "2") (pinfunction "2_2") (pintype "passive"))
      (node (ref "C13") (pin "1") (pinfunction "1_1") (pintype "passive"))
      (node (ref "C14") (pin "2") (pinfunction "2_2") (pintype "passive"))
      (node (ref "C15") (pin "2") (pinfunction "2_2") (pintype "passive"))
      (node (ref "C16") (pin "2") (pinfunction "2_2") (pintype "passive"))
      (node (ref "C17") (pin "2") (pinfunction "2_2") (pintype "passive"))
      (node (ref "C18") (pin "1") (pinfunction "1_1") (pintype "passive"))
      (node (ref "C19") (pin "1") (pinfunction "1_1") (pintype "passive"))
      (node (ref "C2") (pin "2") (pinfunction "2_2") (pintype "passive"))
      (node (ref "C20") (pin "2") (pinfunction "2_2") (pintype "passive"))
      (node (ref "C22") (pin "-") (pinfunction "-_-") (pintype "passive"))
      (node (ref "C27") (pin "2") (pinfunction "2_2") (pintype "passive"))
      (node (ref "C28") (pin "2") (pinfunction "2_2") (pintype "passive"))
      (node (ref "C3") (pin "2") (pinfunction "2_2") (pintype "passive"))
      (node (ref "C4") (pin "1") (pinfunction "1_1") (pintype "passive"))
      (node (ref "C5") (pin "2") (pinfunction "2_2") (pintype "passive"))
      (node (ref "C6") (pin "2") (pinfunction "2_2") (pintype "passive"))
      (node (ref "C7") (pin "1") (pinfunction "1_1") (pintype "passive"))
      (node (ref "C8") (pin "2") (pinfunction "2_2") (pintype "passive"))
      (node (ref "C9") (pin "1") (pinfunction "1_1") (pintype "passive"))
      (node (ref "DC2") (pin "3") (pinfunction "-VOUT_3") (pintype "passive"))
      (node (ref "IC1") (pin "12") (pinfunction "AGND_12") (pintype "power_in"))
      (node (ref "IC1") (pin "19") (pinfunction "DGND_19") (pintype "power_in"))
      (node (ref "IC1") (pin "2") (pinfunction "AGND_2") (pintype "power_in"))
      (node (ref "IC1") (pin "32") (pinfunction "TEST_32") (pintype "power_in"))
      (node (ref "IC1") (pin "36") (pinfunction "DMA_CTRL_36") (pintype "input"))
      (node (ref "IC1") (pin "44") (pinfunction "DGND_44") (pintype "power_in"))
      (node (ref "IC1") (pin "47") (pinfunction "DGND_47") (pintype "power_in"))
      (node (ref "MOV1") (pin "1") (pinfunction "1_1") (pintype "passive"))
      (node (ref "MOV2") (pin "1") (pinfunction "1_1") (pintype "passive"))
      (node (ref "MOV3") (pin "1") (pinfunction "1_1") (pintype "passive"))
      (node (ref "R10") (pin "1") (pinfunction "1_1") (pintype "passive"))
      (node (ref "R11") (pin "1") (pinfunction "1_1") (pintype "passive"))
      (node (ref "R19") (pin "1") (pinfunction "1_1") (pintype "passive"))
      (node (ref "R29") (pin "1") (pinfunction "1_1") (pintype "passive"))
      (node (ref "R36") (pin "1") (pinfunction "1_1") (pintype "passive"))
      (node (ref "R37") (pin "2") (pinfunction "2_2") (pintype "passive"))
      (node (ref "R40") (pin "1") (pinfunction "1_1") (pintype "passive"))
      (node (ref "R41") (pin "2") (pinfunction "2_2") (pintype "passive"))
      (node (ref "R44") (pin "1") (pinfunction "1_1") (pintype "passive"))
      (node (ref "R45") (pin "2") (pinfunction "2_2") (pintype "passive"))
      (node (ref "R8") (pin "1") (pinfunction "1_1") (pintype "passive"))
      (node (ref "R9") (pin "1") (pinfunction "1_1") (pintype "passive"))
      (node (ref "U$4") (pin "AC/N") (pinfunction "AC/N_AC/N") (pintype "input"))
      (node (ref "U$5") (pin "15") (pinfunction "GND2A_15") (pintype "power_in"))
      (node (ref "U$5") (pin "9") (pinfunction "GND2_9") (pintype "power_in"))
      (node (ref "U$6") (pin "P$2") (pinfunction "P$2_P$2") (pintype "bidirectional"))
      (node (ref "U1") (pin "2") (pinfunction "GND_2") (pintype "input"))
      (node (ref "VD2") (pin "A") (pinfunction "A_A") (pintype "passive"))
      (node (ref "VD3") (pin "A") (pinfunction "A_A") (pintype "passive"))
      (node (ref "VD4") (pin "A") (pinfunction "A_A") (pintype "passive"))
      (node (ref "X1") (pin "P$3") (pinfunction "3_P$3") (pintype "passive"))
    )
    (net (code "57") (name "GNDIO") (class "Default")
      (node (ref "C21") (pin "-") (pinfunction "-_-") (pintype "passive"))
      (node (ref "C23") (pin "2") (pinfunction "2_2") (pintype "passive"))
      (node (ref "C24") (pin "2") (pinfunction "2_2") (pintype "passive"))
      (node (ref "C25") (pin "2") (pinfunction "2_2") (pintype "passive"))
      (node (ref "C26") (pin "2") (pinfunction "2_2") (pintype "passive"))
      (node (ref "C29") (pin "2") (pinfunction "2_2") (pintype "passive"))
      (node (ref "C30") (pin "2") (pinfunction "2_2") (pintype "passive"))
      (node (ref "C31") (pin "2") (pinfunction "2_2") (pintype "passive"))
      (node (ref "C32") (pin "2") (pinfunction "2_2") (pintype "passive"))
      (node (ref "C33") (pin "2") (pinfunction "2_2") (pintype "passive"))
      (node (ref "C34") (pin "2") (pinfunction "2_2") (pintype "passive"))
      (node (ref "C35") (pin "1") (pinfunction "1_1") (pintype "passive"))
      (node (ref "C36") (pin "2") (pinfunction "2_2") (pintype "passive"))
      (node (ref "C37") (pin "2") (pinfunction "2_2") (pintype "passive"))
      (node (ref "C38") (pin "2") (pinfunction "2_2") (pintype "passive"))
      (node (ref "C39") (pin "2") (pinfunction "2_2") (pintype "passive"))
      (node (ref "C40") (pin "-") (pinfunction "-_-") (pintype "passive"))
      (node (ref "DC1") (pin "2") (pinfunction "-VIN_2") (pintype "passive"))
      (node (ref "DC1") (pin "5") (pinfunction "COM_5") (pintype "passive"))
      (node (ref "DC2") (pin "1") (pinfunction "-VIN_1") (pintype "passive"))
      (node (ref "J1") (pin "4") (pinfunction "4_4") (pintype "passive"))
      (node (ref "J2") (pin "1") (pinfunction "1_1") (pintype "passive"))
      (node (ref "Q2") (pin "2") (pinfunction "S_2") (pintype "bidirectional"))
      (node (ref "R46") (pin "1") (pinfunction "1_1") (pintype "passive"))
      (node (ref "R49") (pin "2") (pinfunction "2_2") (pintype "passive"))
      (node (ref "R53") (pin "1") (pinfunction "1_1") (pintype "passive"))
      (node (ref "R60") (pin "1") (pinfunction "1_1") (pintype "passive"))
      (node (ref "R64") (pin "1") (pinfunction "1_1") (pintype "passive"))
      (node (ref "TP5") (pin "P$1") (pinfunction "1_P$1") (pintype "bidirectional"))
      (node (ref "U$4") (pin "V-") (pinfunction "V-_V-") (pintype "output"))
      (node (ref "U$5") (pin "2") (pinfunction "GND1A_2") (pintype "power_in"))
      (node (ref "U$5") (pin "8") (pinfunction "GND1_8") (pintype "power_in"))
      (node (ref "U$8") (pin "10") (pinfunction "P$10_10") (pintype "bidirectional"))
      (node (ref "U$8") (pin "11") (pinfunction "P$11_11") (pintype "bidirectional"))
      (node (ref "U$8") (pin "12") (pinfunction "P$12_12") (pintype "bidirectional"))
      (node (ref "U$8") (pin "9") (pinfunction "P$9_9") (pintype "bidirectional"))
      (node (ref "U2") (pin "20") (pinfunction "PB2_20") (pintype "bidirectional"))
      (node (ref "U2") (pin "23") (pinfunction "VSS_1_23") (pintype "bidirectional"))
      (node (ref "U2") (pin "35") (pinfunction "VSS_2_35") (pintype "passive"))
      (node (ref "U2") (pin "47") (pinfunction "VSS_3_47") (pintype "passive"))
      (node (ref "U2") (pin "8") (pinfunction "VSSA_8") (pintype "passive"))
      (node (ref "U3") (pin "2") (pinfunction "GND_2") (pintype "input"))
      (node (ref "U4") (pin "5") (pinfunction "GND_5") (pintype "bidirectional"))
      (node (ref "X3") (pin "GND") (pinfunction "GND_GND") (pintype "bidirectional"))
    )
    (net (code "58") (name "Net-(C18-Pad2)") (class "Default")
      (node (ref "C18") (pin "2") (pinfunction "2_2") (pintype "passive"))
      (node (ref "C19") (pin "2") (pinfunction "2_2") (pintype "passive"))
      (node (ref "IC1") (pin "42") (pinfunction "VDD18_42") (pintype "power_in"))
      (node (ref "IC1") (pin "43") (pinfunction "VDD18_43") (pintype "power_in"))
    )
    (net (code "59") (name "Net-(IC1-OSCI)") (class "Default")
      (node (ref "C10") (pin "1") (pinfunction "1_1") (pintype "passive"))
      (node (ref "IC1") (pin "20") (pinfunction "OSCI_20") (pintype "input"))
      (node (ref "Y1") (pin "1") (pinfunction "1_1") (pintype "passive"))
    )
    (net (code "60") (name "Net-(IC1-OSCO)") (class "Default")
      (node (ref "C11") (pin "1") (pinfunction "1_1") (pintype "passive"))
      (node (ref "IC1") (pin "21") (pinfunction "OSCO_21") (pintype "output"))
      (node (ref "Y1") (pin "3") (pinfunction "2_3") (pintype "passive"))
    )
    (net (code "61") (name "Net-(IC1-V1N)") (class "Default")
      (node (ref "C14") (pin "1") (pinfunction "1_1") (pintype "passive"))
      (node (ref "IC1") (pin "14") (pinfunction "V1N_14") (pintype "input"))
      (node (ref "R9") (pin "2") (pinfunction "2_2") (pintype "passive"))
    )
    (net (code "62") (name "Net-(IC1-V2N)") (class "Default")
      (node (ref "C16") (pin "1") (pinfunction "1_1") (pintype "passive"))
      (node (ref "IC1") (pin "16") (pinfunction "V2N_16") (pintype "input"))
      (node (ref "R10") (pin "2") (pinfunction "2_2") (pintype "passive"))
    )
    (net (code "63") (name "Net-(IC1-V3N)") (class "Default")
      (node (ref "C20") (pin "1") (pinfunction "1_1") (pintype "passive"))
      (node (ref "IC1") (pin "18") (pinfunction "V3N_18") (pintype "input"))
      (node (ref "R11") (pin "2") (pinfunction "2_2") (pintype "passive"))
    )
    (net (code "64") (name "Net-(IC1-VREF)") (class "Default")
      (node (ref "C12") (pin "1") (pinfunction "1_1") (pintype "passive"))
      (node (ref "C15") (pin "1") (pinfunction "1_1") (pintype "passive"))
      (node (ref "IC1") (pin "11") (pinfunction "VREF_11") (pintype "bidirectional"))
    )
    (net (code "65") (name "Net-(IC1-~{RESET})") (class "Default")
      (node (ref "IC1") (pin "41") (pinfunction "~{RESET}_41") (pintype "input"))
      (node (ref "R20") (pin "2") (pinfunction "2_2") (pintype "passive"))
    )
    (net (code "66") (name "Net-(MOV2-Pad2)") (class "Default")
      (node (ref "MOV2") (pin "2") (pinfunction "2_2") (pintype "passive"))
      (node (ref "R12") (pin "1") (pinfunction "1_1") (pintype "passive"))
      (node (ref "U$2") (pin "P$1") (pinfunction "P$1_P$1") (pintype "bidirectional"))
    )
    (net (code "67") (name "Net-(MOV3-Pad2)") (class "Default")
      (node (ref "MOV3") (pin "2") (pinfunction "2_2") (pintype "passive"))
      (node (ref "R22") (pin "1") (pinfunction "1_1") (pintype "passive"))
      (node (ref "U$3") (pin "P$1") (pinfunction "P$1_P$1") (pintype "bidirectional"))
    )
    (net (code "68") (name "Net-(Q2-D)") (class "Default")
      (node (ref "J1") (pin "2") (pinfunction "2_2") (pintype "passive"))
      (node (ref "Q2") (pin "3") (pinfunction "D_3") (pintype "bidirectional"))
      (node (ref "R67") (pin "1") (pinfunction "1_1") (pintype "passive"))
    )
    (net (code "69") (name "Net-(R1-Pad2)") (class "Default")
      (node (ref "R1") (pin "2") (pinfunction "2_2") (pintype "passive"))
      (node (ref "R2") (pin "1") (pinfunction "1_1") (pintype "passive"))
    )
    (net (code "70") (name "Net-(R2-Pad2)") (class "Default")
      (node (ref "R2") (pin "2") (pinfunction "2_2") (pintype "passive"))
      (node (ref "R3") (pin "1") (pinfunction "1_1") (pintype "passive"))
    )
    (net (code "71") (name "Net-(R3-Pad2)") (class "Default")
      (node (ref "R3") (pin "2") (pinfunction "2_2") (pintype "passive"))
      (node (ref "R4") (pin "1") (pinfunction "1_1") (pintype "passive"))
    )
    (net (code "72") (name "Net-(R4-Pad2)") (class "Default")
      (node (ref "R4") (pin "2") (pinfunction "2_2") (pintype "passive"))
      (node (ref "R5") (pin "1") (pinfunction "1_1") (pintype "passive"))
    )
    (net (code "73") (name "Net-(R5-Pad2)") (class "Default")
      (node (ref "R5") (pin "2") (pinfunction "2_2") (pintype "passive"))
      (node (ref "R6") (pin "1") (pinfunction "1_1") (pintype "passive"))
    )
    (net (code "74") (name "Net-(R6-Pad2)") (class "Default")
      (node (ref "R6") (pin "2") (pinfunction "2_2") (pintype "passive"))
      (node (ref "R7") (pin "1") (pinfunction "1_1") (pintype "passive"))
    )
    (net (code "75") (name "Net-(R12-Pad2)") (class "Default")
      (node (ref "R12") (pin "2") (pinfunction "2_2") (pintype "passive"))
      (node (ref "R13") (pin "1") (pinfunction "1_1") (pintype "passive"))
    )
    (net (code "76") (name "Net-(R13-Pad2)") (class "Default")
      (node (ref "R13") (pin "2") (pinfunction "2_2") (pintype "passive"))
      (node (ref "R14") (pin "1") (pinfunction "1_1") (pintype "passive"))
    )
    (net (code "77") (name "Net-(R14-Pad2)") (class "Default")
      (node (ref "R14") (pin "2") (pinfunction "2_2") (pintype "passive"))
      (node (ref "R15") (pin "1") (pinfunction "1_1") (pintype "passive"))
    )
    (net (code "78") (name "Net-(R15-Pad2)") (class "Default")
      (node (ref "R15") (pin "2") (pinfunction "2_2") (pintype "passive"))
      (node (ref "R16") (pin "1") (pinfunction "1_1") (pintype "passive"))
    )
    (net (code "79") (name "Net-(R16-Pad2)") (class "Default")
      (node (ref "R16") (pin "2") (pinfunction "2_2") (pintype "passive"))
      (node (ref "R17") (pin "1") (pinfunction "1_1") (pintype "passive"))
    )
    (net (code "80") (name "Net-(R17-Pad2)") (class "Default")
      (node (ref "R17") (pin "2") (pinfunction "2_2") (pintype "passive"))
      (node (ref "R18") (pin "1") (pinfunction "1_1") (pintype "passive"))
    )
    (net (code "81") (name "Net-(R22-Pad2)") (class "Default")
      (node (ref "R22") (pin "2") (pinfunction "2_2") (pintype "passive"))
      (node (ref "R23") (pin "1") (pinfunction "1_1") (pintype "passive"))
    )
    (net (code "82") (name "Net-(R23-Pad2)") (class "Default")
      (node (ref "R23") (pin "2") (pinfunction "2_2") (pintype "passive"))
      (node (ref "R24") (pin "1") (pinfunction "1_1") (pintype "passive"))
    )
    (net (code "83") (name "Net-(R24-Pad2)") (class "Default")
      (node (ref "R24") (pin "2") (pinfunction "2_2") (pintype "passive"))
      (node (ref "R25") (pin "1") (pinfunction "1_1") (pintype "passive"))
    )
    (net (code "84") (name "Net-(R25-Pad2)") (class "Default")
      (node (ref "R25") (pin "2") (pinfunction "2_2") (pintype "passive"))
      (node (ref "R26") (pin "1") (pinfunction "1_1") (pintype "passive"))
    )
    (net (code "85") (name "Net-(R26-Pad2)") (class "Default")
      (node (ref "R26") (pin "2") (pinfunction "2_2") (pintype "passive"))
      (node (ref "R27") (pin "1") (pinfunction "1_1") (pintype "passive"))
    )
    (net (code "86") (name "Net-(R27-Pad2)") (class "Default")
      (node (ref "R27") (pin "2") (pinfunction "2_2") (pintype "passive"))
      (node (ref "R28") (pin "1") (pinfunction "1_1") (pintype "passive"))
    )
    (net (code "87") (name "Net-(R55-Pad1)") (class "Default")
      (node (ref "R55") (pin "1") (pinfunction "1_1") (pintype "passive"))
      (node (ref "X3") (pin "D+") (pinfunction "D+_D+") (pintype "bidirectional"))
    )
    (net (code "88") (name "Net-(R57-Pad1)") (class "Default")
      (node (ref "R57") (pin "1") (pinfunction "1_1") (pintype "passive"))
      (node (ref "X3") (pin "D-") (pinfunction "D-_D-") (pintype "bidirectional"))
    )
    (net (code "89") (name "Net-(U$5-A1)") (class "Default")
      (node (ref "U$5") (pin "3") (pinfunction "A1_3") (pintype "input"))
      (node (ref "U2") (pin "42") (pinfunction "PB6_42") (pintype "bidirectional"))
    )
    (net (code "90") (name "Net-(U$5-A2)") (class "Default")
      (node (ref "U$5") (pin "4") (pinfunction "A2_4") (pintype "input"))
      (node (ref "U2") (pin "39") (pinfunction "PB3_39") (pintype "bidirectional"))
    )
    (net (code "91") (name "Net-(U$5-A3)") (class "Default")
      (node (ref "U$5") (pin "5") (pinfunction "A3_5") (pintype "input"))
      (node (ref "U2") (pin "41") (pinfunction "PB5_41") (pintype "bidirectional"))
    )
    (net (code "92") (name "Net-(U$5-A4)") (class "Default")
      (node (ref "U$5") (pin "6") (pinfunction "A4_6") (pintype "input"))
      (node (ref "U2") (pin "40") (pinfunction "PB4_40") (pintype "bidirectional"))
    )
    (net (code "93") (name "Net-(U$10A-+IN)") (class "Default")
      (node (ref "C34") (pin "1") (pinfunction "1_1") (pintype "passive"))
      (node (ref "R49") (pin "1") (pinfunction "1_1") (pintype "passive"))
      (node (ref "R50") (pin "2") (pinfunction "2_2") (pintype "passive"))
      (node (ref "U$10") (pin "3") (pinfunction "+IN_3") (pintype "input"))
      (node (ref "U$10") (pin "5") (pinfunction "+IN_5") (pintype "input"))
    )
    (net (code "94") (name "Net-(U$10A--IN)") (class "Default")
      (node (ref "R56") (pin "1") (pinfunction "1_1") (pintype "passive"))
      (node (ref "U$10") (pin "2") (pinfunction "-IN_2") (pintype "input"))
    )
    (net (code "95") (name "Net-(U$10A-OUT)") (class "Default")
      (node (ref "R51") (pin "2") (pinfunction "2_2") (pintype "passive"))
      (node (ref "U$10") (pin "1") (pinfunction "OUT_1") (pintype "output"))
    )
    (net (code "96") (name "Net-(U$10B--IN)") (class "Default")
      (node (ref "R48") (pin "1") (pinfunction "1_1") (pintype "passive"))
      (node (ref "U$10") (pin "6") (pinfunction "-IN_6") (pintype "input"))
    )
    (net (code "97") (name "Net-(U$10B-OUT)") (class "Default")
      (node (ref "R32") (pin "2") (pinfunction "2_2") (pintype "passive"))
      (node (ref "U$10") (pin "7") (pinfunction "OUT_7") (pintype "output"))
    )
    (net (code "98") (name "Net-(U2-PA2)") (class "Default")
      (node (ref "U2") (pin "12") (pinfunction "PA2_12") (pintype "bidirectional"))
      (node (ref "U4") (pin "4") (pinfunction "DI_4") (pintype "bidirectional"))
    )
    (net (code "99") (name "Net-(U2-PA3)") (class "Default")
      (node (ref "U2") (pin "13") (pinfunction "PA3_13") (pintype "bidirectional"))
      (node (ref "U4") (pin "1") (pinfunction "RO_1") (pintype "bidirectional"))
    )
    (net (code "100") (name "Net-(U2-PA4)") (class "Default")
      (node (ref "U2") (pin "14") (pinfunction "PA4_14") (pintype "bidirectional"))
      (node (ref "U4") (pin "2") (pinfunction "/RE_2") (pintype "bidirectional"))
      (node (ref "U4") (pin "3") (pinfunction "DE_3") (pintype "bidirectional"))
    )
    (net (code "101") (name "Net-(U2-PA11)") (class "Default")
      (node (ref "R57") (pin "2") (pinfunction "2_2") (pintype "passive"))
      (node (ref "U2") (pin "32") (pinfunction "PA11_32") (pintype "power_in"))
    )
    (net (code "102") (name "Net-(U2-PA12)") (class "Default")
      (node (ref "R55") (pin "2") (pinfunction "2_2") (pintype "passive"))
      (node (ref "R58") (pin "1") (pinfunction "1_1") (pintype "passive"))
      (node (ref "U2") (pin "33") (pinfunction "PA12_33") (pintype "bidirectional"))
    )
    (net (code "103") (name "Net-(U2-PD0-OSC_IN)") (class "Default")
      (node (ref "C32") (pin "1") (pinfunction "1_1") (pintype "passive"))
      (node (ref "U2") (pin "5") (pinfunction "PD0-OSC_IN_5") (pintype "bidirectional"))
      (node (ref "Y2") (pin "3") (pinfunction "2_3") (pintype "passive"))
    )
    (net (code "104") (name "Net-(U2-PD1-OSC_OUT)") (class "Default")
      (node (ref "C33") (pin "1") (pinfunction "1_1") (pintype "passive"))
      (node (ref "U2") (pin "6") (pinfunction "PD1-OSC_OUT_6") (pintype "bidirectional"))
      (node (ref "Y2") (pin "1") (pinfunction "1_1") (pintype "passive"))
    )
    (net (code "105") (name "Net-(X1-1)") (class "Default")
      (node (ref "U$1") (pin "P$1") (pinfunction "P$1_P$1") (pintype "bidirectional"))
      (node (ref "U$6") (pin "P$1") (pinfunction "P$1_P$1") (pintype "bidirectional"))
      (node (ref "X1") (pin "P$1") (pinfunction "1_P$1") (pintype "passive"))
    )
    (net (code "106") (name "Net-(X1-2)") (class "Default")
      (node (ref "U$2") (pin "P$2") (pinfunction "P$2_P$2") (pintype "bidirectional"))
      (node (ref "X1") (pin "P$2") (pinfunction "2_P$2") (pintype "passive"))
    )
    (net (code "107") (name "Net-(X1-4)") (class "Default")
      (node (ref "U$3") (pin "P$2") (pinfunction "P$2_P$2") (pintype "bidirectional"))
      (node (ref "X1") (pin "P$4") (pinfunction "4_P$4") (pintype "passive"))
    )
    (net (code "108") (name "Net-(X2-1)") (class "Default")
      (node (ref "R42") (pin "1") (pinfunction "1_1") (pintype "passive"))
      (node (ref "R44") (pin "2") (pinfunction "2_2") (pintype "passive"))
      (node (ref "X2") (pin "P$1") (pinfunction "1_P$1") (pintype "passive"))
    )
    (net (code "109") (name "Net-(X2-2)") (class "Default")
      (node (ref "R38") (pin "1") (pinfunction "1_1") (pintype "passive"))
      (node (ref "R40") (pin "2") (pinfunction "2_2") (pintype "passive"))
      (node (ref "X2") (pin "P$2") (pinfunction "2_P$2") (pintype "passive"))
    )
    (net (code "110") (name "Net-(X2-3)") (class "Default")
      (node (ref "R34") (pin "1") (pinfunction "1_1") (pintype "passive"))
      (node (ref "R36") (pin "2") (pinfunction "2_2") (pintype "passive"))
      (node (ref "X2") (pin "P$3") (pinfunction "3_P$3") (pintype "passive"))
    )
    (net (code "111") (name "Net-(X2-4)") (class "Default")
      (node (ref "R43") (pin "1") (pinfunction "1_1") (pintype "passive"))
      (node (ref "R45") (pin "1") (pinfunction "1_1") (pintype "passive"))
      (node (ref "X2") (pin "P$4") (pinfunction "4_P$4") (pintype "passive"))
    )
    (net (code "112") (name "Net-(X2-5)") (class "Default")
      (node (ref "R39") (pin "1") (pinfunction "1_1") (pintype "passive"))
      (node (ref "R41") (pin "1") (pinfunction "1_1") (pintype "passive"))
      (node (ref "X2") (pin "P$5") (pinfunction "5_P$5") (pintype "passive"))
    )
    (net (code "113") (name "Net-(X2-6)") (class "Default")
      (node (ref "R35") (pin "1") (pinfunction "1_1") (pintype "passive"))
      (node (ref "R37") (pin "1") (pinfunction "1_1") (pintype "passive"))
      (node (ref "X2") (pin "P$6") (pinfunction "6_P$6") (pintype "passive"))
    )
    (net (code "114") (name "VCC") (class "Default")
      (node (ref "C21") (pin "+") (pinfunction "+_+") (pintype "passive"))
      (node (ref "C25") (pin "1") (pinfunction "1_1") (pintype "passive"))
      (node (ref "C26") (pin "1") (pinfunction "1_1") (pintype "passive"))
      (node (ref "C29") (pin "1") (pinfunction "1_1") (pintype "passive"))
      (node (ref "C38") (pin "1") (pinfunction "1_1") (pintype "passive"))
      (node (ref "C39") (pin "1") (pinfunction "1_1") (pintype "passive"))
      (node (ref "C40") (pin "+") (pinfunction "+_+") (pintype "passive"))
      (node (ref "DC1") (pin "1") (pinfunction "+VIN_1") (pintype "passive"))
      (node (ref "DC2") (pin "2") (pinfunction "+VIN_2") (pintype "passive"))
      (node (ref "R31") (pin "1") (pinfunction "1_1") (pintype "passive"))
      (node (ref "U$4") (pin "V+") (pinfunction "V+_V+") (pintype "output"))
      (node (ref "U$8") (pin "5") (pinfunction "P$5_5") (pintype "bidirectional"))
      (node (ref "U$8") (pin "6") (pinfunction "P$6_6") (pintype "bidirectional"))
      (node (ref "U$8") (pin "7") (pinfunction "P$7_7") (pintype "bidirectional"))
      (node (ref "U$8") (pin "8") (pinfunction "P$8_8") (pintype "bidirectional"))
      (node (ref "U3") (pin "1") (pinfunction "IN_1") (pintype "input"))
      (node (ref "U3") (pin "3") (pinfunction "EN_3") (pintype "input"))
    )
    (net (code "115") (name "VDD") (class "Default")
      (node (ref "C13") (pin "2") (pinfunction "2_2") (pintype "passive"))
      (node (ref "C17") (pin "1") (pinfunction "1_1") (pintype "passive"))
      (node (ref "C22") (pin "+") (pinfunction "+_+") (pintype "passive"))
      (node (ref "IC1") (pin "1") (pinfunction "AVDD_1") (pintype "power_in"))
      (node (ref "IC1") (pin "33") (pinfunction "PM0_33") (pintype "input"))
      (node (ref "IC1") (pin "34") (pinfunction "PM1_34") (pintype "input"))
      (node (ref "IC1") (pin "48") (pinfunction "DVDD_48") (pintype "power_in"))
      (node (ref "R20") (pin "1") (pinfunction "1_1") (pintype "passive"))
      (node (ref "R21") (pin "5") (pinfunction "5_5") (pintype "bidirectional"))
      (node (ref "R21") (pin "6") (pinfunction "6_6") (pintype "bidirectional"))
      (node (ref "R21") (pin "7") (pinfunction "7_7") (pintype "bidirectional"))
      (node (ref "R21") (pin "8") (pinfunction "8_8") (pintype "bidirectional"))
      (node (ref "U$5") (pin "10") (pinfunction "EN2_10") (pintype "input"))
      (node (ref "U$5") (pin "16") (pinfunction "VDD2_16") (pintype "power_in"))
      (node (ref "U1") (pin "5") (pinfunction "OUT_5") (pintype "passive"))
    )
    (net (code "116") (name "unconnected-(IC1-NC-Pad35)") (class "Default")
      (node (ref "IC1") (pin "35") (pinfunction "NC_35") (pintype "no_connect"))
    )
    (net (code "117") (name "unconnected-(IC1-NC-Pad45)") (class "Default")
      (node (ref "IC1") (pin "45") (pinfunction "NC_45") (pintype "no_connect"))
    )
    (net (code "118") (name "unconnected-(IC1-NC-Pad46)") (class "Default")
      (node (ref "IC1") (pin "46") (pinfunction "NC_46") (pintype "no_connect"))
    )
    (net (code "119") (name "unconnected-(IC1-ZX0-Pad22)") (class "Default")
      (node (ref "IC1") (pin "22") (pinfunction "ZX0_22") (pintype "output"))
    )
    (net (code "120") (name "unconnected-(IC1-ZX1-Pad23)") (class "Default")
      (node (ref "IC1") (pin "23") (pinfunction "ZX1_23") (pintype "output"))
    )
    (net (code "121") (name "unconnected-(IC1-ZX2-Pad24)") (class "Default")
      (node (ref "IC1") (pin "24") (pinfunction "ZX2_24") (pintype "output"))
    )
    (net (code "122") (name "unconnected-(J2-Pad5)") (class "Default")
      (node (ref "J2") (pin "5") (pinfunction "5_5") (pintype "passive"))
    )
    (net (code "123") (name "unconnected-(U1-NC-Pad4)") (class "Default")
      (node (ref "U1") (pin "4") (pinfunction "NC_4") (pintype "no_connect"))
    )
    (net (code "124") (name "unconnected-(U2-PA8-Pad29)") (class "Default")
      (node (ref "U2") (pin "29") (pinfunction "PA8_29") (pintype "bidirectional"))
    )
    (net (code "125") (name "unconnected-(U2-PB7-Pad43)") (class "Default")
      (node (ref "U2") (pin "43") (pinfunction "PB7_43") (pintype "bidirectional"))
    )
    (net (code "126") (name "unconnected-(U2-PC14-OSC32_IN-Pad3)") (class "Default")
      (node (ref "U2") (pin "3") (pinfunction "PC14-OSC32_IN_3") (pintype "bidirectional"))
    )
    (net (code "127") (name "unconnected-(U2-PC15-OSC32_OUT-Pad4)") (class "Default")
      (node (ref "U2") (pin "4") (pinfunction "PC15-OSC32_OUT_4") (pintype "bidirectional"))
    )
    (net (code "128") (name "unconnected-(U3-NC-Pad4)") (class "Default")
      (node (ref "U3") (pin "4") (pinfunction "NC_4") (pintype "no_connect"))
    )
    (net (code "129") (name "unconnected-(X3-PadVBUS)") (class "Default")
      (node (ref "X3") (pin "VBUS") (pinfunction "VBUS_VBUS") (pintype "bidirectional"))
    )
  )
)
